# design.net
KiCad netlist of a schematic drawn in EasyEDA
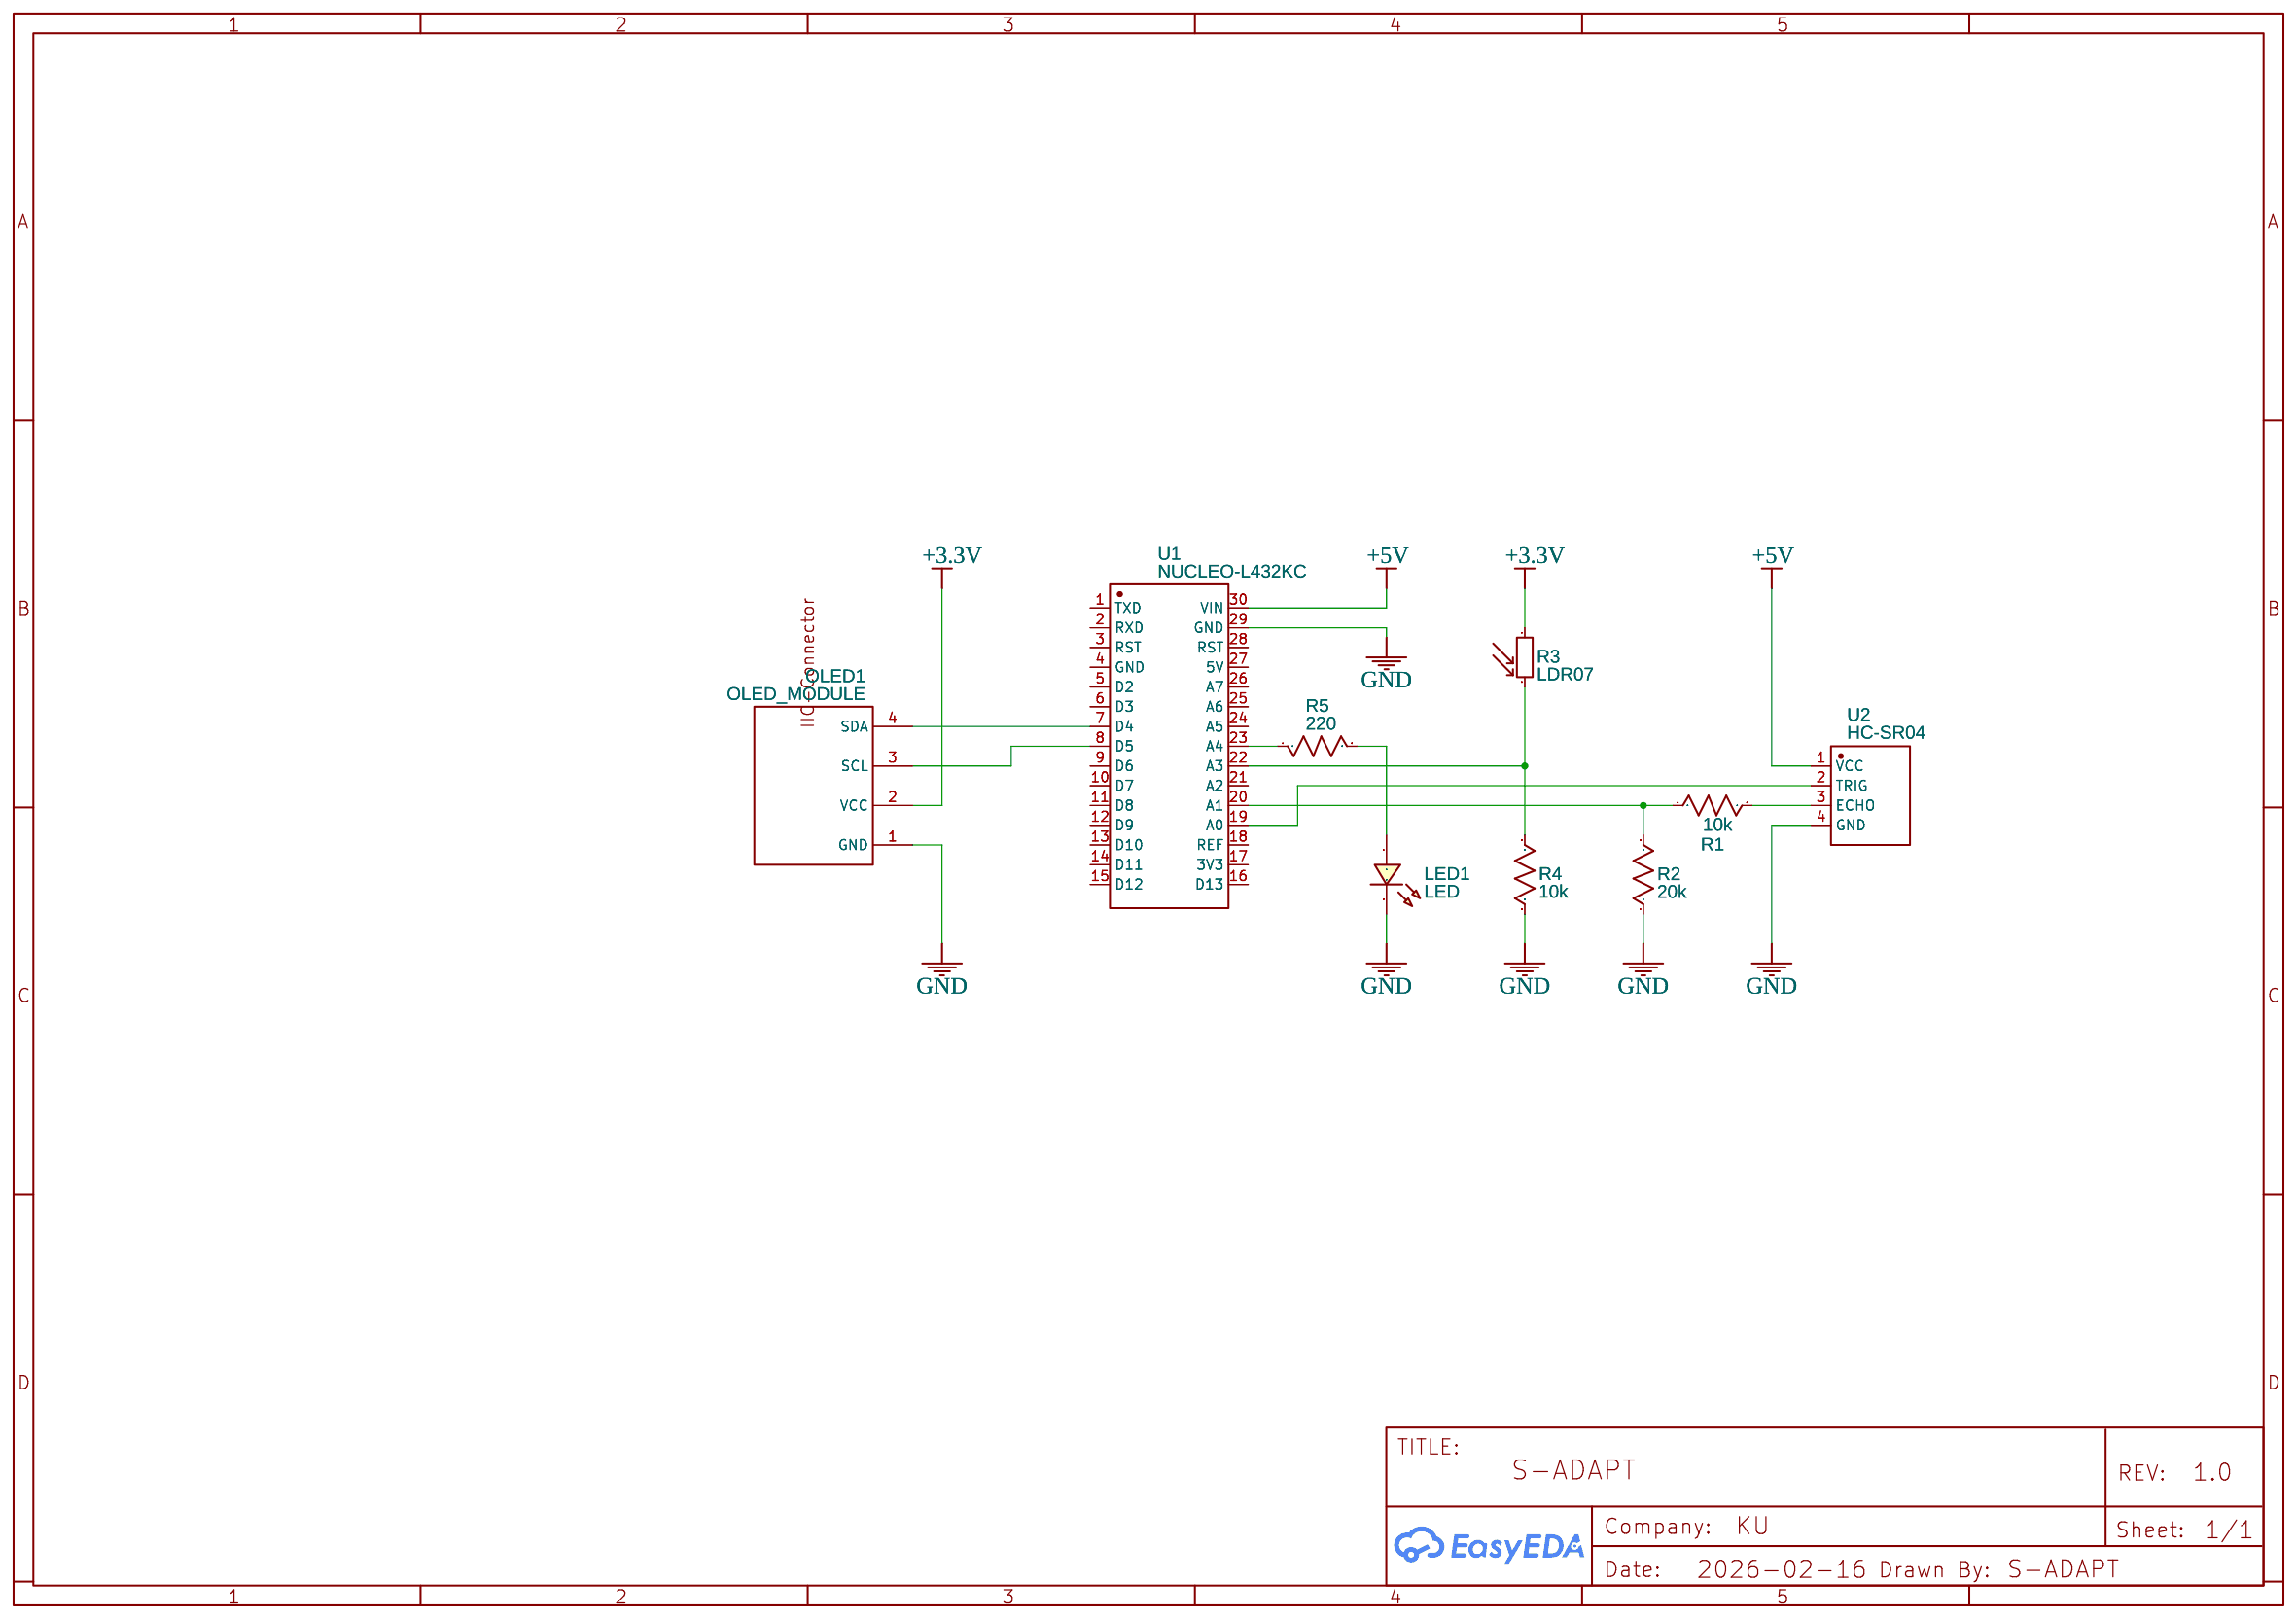
[diagram p0: schematic sheet]

(export (version "E")
  (design (tool "Eeschema 10.0.6"))
  (components
    (comp (ref "LED1")
      (value "LED")
      (fields
        (field (name "Manufacturer Part") "19-217/R6C-AL1M2VY/3T")
        (field (name "Manufacturer") "EVERLIGHT(台湾亿光)")
      )
      (libsource (lib "") (part "LED-0603_R"))
    )
    (comp (ref "OLED1")
      (value "OLED_MODULE")
      (fields (field (name "Manufacturer Part") "0.96OLED_4P_MODULE_JX"))
      (libsource (lib "") (part "0.96OLED_4P_MODULE_JX"))
    )
    (comp (ref "R1") (value "10k") (libsource (lib "") (part "R_0603_US_3")))
    (comp (ref "R2") (value "20k") (libsource (lib "") (part "R_0603_US")))
    (comp (ref "R3") (value "LDR07") (libsource (lib "") (part "LDR07")))
    (comp (ref "R4") (value "10k") (libsource (lib "") (part "R_0603_US_2")))
    (comp (ref "R5") (value "220") (libsource (lib "") (part "R_0603_US_1")))
    (comp (ref "U1")
      (value "NUCLEO-L432KC")
      (fields (field (name "Manufacturer") "ST(意法半导体)"))
      (libsource (lib "") (part "NUCLEO-L432KC"))
    )
    (comp (ref "U2")
      (value "HC-SR04")
      (fields (field (name "Manufacturer") "Universal Microelectronics"))
      (libsource (lib "") (part "HC-SR04"))
    )
  )
  (nets
    (net (code "1") (name "+3.3V") (class "Default")
      (node (ref "OLED1") (pin "2") (pinfunction "VCC_2") (pintype "unspecified"))
      (node (ref "R3") (pin "1") (pintype "unspecified"))
    )
    (net (code "2") (name "+5V") (class "Default")
      (node (ref "U1") (pin "30") (pinfunction "VIN_30") (pintype "unspecified"))
      (node (ref "U2") (pin "1") (pinfunction "VCC_1") (pintype "unspecified"))
    )
    (net (code "3") (name "GND") (class "Default")
      (node (ref "LED1") (pin "2") (pinfunction "2_2") (pintype "unspecified"))
      (node (ref "OLED1") (pin "1") (pinfunction "GND_1") (pintype "unspecified"))
      (node (ref "R2") (pin "1") (pinfunction "1_1") (pintype "unspecified"))
      (node (ref "R4") (pin "2") (pinfunction "2_2") (pintype "unspecified"))
      (node (ref "U1") (pin "29") (pinfunction "GND_29") (pintype "unspecified"))
      (node (ref "U2") (pin "4") (pinfunction "GND_4") (pintype "unspecified"))
    )
    (net (code "4") (name "Net-(LED1-Pad1)") (class "Default")
      (node (ref "LED1") (pin "1") (pinfunction "1_1") (pintype "unspecified"))
      (node (ref "R5") (pin "2") (pinfunction "2_2") (pintype "unspecified"))
    )
    (net (code "5") (name "Net-(OLED1-SCL)") (class "Default")
      (node (ref "OLED1") (pin "3") (pinfunction "SCL_3") (pintype "unspecified"))
      (node (ref "U1") (pin "8") (pinfunction "D5_8") (pintype "unspecified"))
    )
    (net (code "6") (name "Net-(OLED1-SDA)") (class "Default")
      (node (ref "OLED1") (pin "4") (pinfunction "SDA_4") (pintype "unspecified"))
      (node (ref "U1") (pin "7") (pinfunction "D4_7") (pintype "unspecified"))
    )
    (net (code "7") (name "Net-(U1-A0)") (class "Default")
      (node (ref "U1") (pin "19") (pinfunction "A0_19") (pintype "unspecified"))
      (node (ref "U2") (pin "2") (pinfunction "TRIG_2") (pintype "unspecified"))
    )
    (net (code "8") (name "Net-(U1-A1)") (class "Default")
      (node (ref "R1") (pin "2") (pinfunction "2_2") (pintype "unspecified"))
      (node (ref "R2") (pin "2") (pinfunction "2_2") (pintype "unspecified"))
      (node (ref "U1") (pin "20") (pinfunction "A1_20") (pintype "unspecified"))
    )
    (net (code "9") (name "Net-(U1-A3)") (class "Default")
      (node (ref "R3") (pin "2") (pintype "unspecified"))
      (node (ref "R4") (pin "1") (pinfunction "1_1") (pintype "unspecified"))
      (node (ref "U1") (pin "22") (pinfunction "A3_22") (pintype "unspecified"))
    )
    (net (code "10") (name "Net-(U1-A4)") (class "Default")
      (node (ref "R5") (pin "1") (pinfunction "1_1") (pintype "unspecified"))
      (node (ref "U1") (pin "23") (pinfunction "A4_23") (pintype "unspecified"))
    )
    (net (code "11") (name "Net-(U2-ECHO)") (class "Default")
      (node (ref "R1") (pin "1") (pinfunction "1_1") (pintype "unspecified"))
      (node (ref "U2") (pin "3") (pinfunction "ECHO_3") (pintype "unspecified"))
    )
    (net (code "12") (name "unconnected-(U1-3V3-Pad17)") (class "Default")
      (node (ref "U1") (pin "17") (pinfunction "3V3_17") (pintype "unspecified"))
    )
    (net (code "13") (name "unconnected-(U1-5V-Pad27)") (class "Default")
      (node (ref "U1") (pin "27") (pinfunction "5V_27") (pintype "unspecified"))
    )
    (net (code "14") (name "unconnected-(U1-A2-Pad21)") (class "Default")
      (node (ref "U1") (pin "21") (pinfunction "A2_21") (pintype "unspecified"))
    )
    (net (code "15") (name "unconnected-(U1-A5-Pad24)") (class "Default")
      (node (ref "U1") (pin "24") (pinfunction "A5_24") (pintype "unspecified"))
    )
    (net (code "16") (name "unconnected-(U1-A6-Pad25)") (class "Default")
      (node (ref "U1") (pin "25") (pinfunction "A6_25") (pintype "unspecified"))
    )
    (net (code "17") (name "unconnected-(U1-A7-Pad26)") (class "Default")
      (node (ref "U1") (pin "26") (pinfunction "A7_26") (pintype "unspecified"))
    )
    (net (code "18") (name "unconnected-(U1-D2-Pad5)") (class "Default")
      (node (ref "U1") (pin "5") (pinfunction "D2_5") (pintype "unspecified"))
    )
    (net (code "19") (name "unconnected-(U1-D3-Pad6)") (class "Default")
      (node (ref "U1") (pin "6") (pinfunction "D3_6") (pintype "unspecified"))
    )
    (net (code "20") (name "unconnected-(U1-D6-Pad9)") (class "Default")
      (node (ref "U1") (pin "9") (pinfunction "D6_9") (pintype "unspecified"))
    )
    (net (code "21") (name "unconnected-(U1-D7-Pad10)") (class "Default")
      (node (ref "U1") (pin "10") (pinfunction "D7_10") (pintype "unspecified"))
    )
    (net (code "22") (name "unconnected-(U1-D8-Pad11)") (class "Default")
      (node (ref "U1") (pin "11") (pinfunction "D8_11") (pintype "unspecified"))
    )
    (net (code "23") (name "unconnected-(U1-D9-Pad12)") (class "Default")
      (node (ref "U1") (pin "12") (pinfunction "D9_12") (pintype "unspecified"))
    )
    (net (code "24") (name "unconnected-(U1-D10-Pad13)") (class "Default")
      (node (ref "U1") (pin "13") (pinfunction "D10_13") (pintype "unspecified"))
    )
    (net (code "25") (name "unconnected-(U1-D11-Pad14)") (class "Default")
      (node (ref "U1") (pin "14") (pinfunction "D11_14") (pintype "unspecified"))
    )
    (net (code "26") (name "unconnected-(U1-D12-Pad15)") (class "Default")
      (node (ref "U1") (pin "15") (pinfunction "D12_15") (pintype "unspecified"))
    )
    (net (code "27") (name "unconnected-(U1-D13-Pad16)") (class "Default")
      (node (ref "U1") (pin "16") (pinfunction "D13_16") (pintype "unspecified"))
    )
    (net (code "28") (name "unconnected-(U1-GND-Pad4)") (class "Default")
      (node (ref "U1") (pin "4") (pinfunction "GND_4") (pintype "unspecified"))
    )
    (net (code "29") (name "unconnected-(U1-REF-Pad18)") (class "Default")
      (node (ref "U1") (pin "18") (pinfunction "REF_18") (pintype "unspecified"))
    )
    (net (code "30") (name "unconnected-(U1-RST-Pad3)") (class "Default")
      (node (ref "U1") (pin "3") (pinfunction "RST_3") (pintype "unspecified"))
    )
    (net (code "31") (name "unconnected-(U1-RST-Pad28)") (class "Default")
      (node (ref "U1") (pin "28") (pinfunction "RST_28") (pintype "unspecified"))
    )
    (net (code "32") (name "unconnected-(U1-RXD-Pad2)") (class "Default")
      (node (ref "U1") (pin "2") (pinfunction "RXD_2") (pintype "unspecified"))
    )
    (net (code "33") (name "unconnected-(U1-TXD-Pad1)") (class "Default")
      (node (ref "U1") (pin "1") (pinfunction "TXD_1") (pintype "unspecified"))
    )
  )
)
